# fullAdder.net
KiCad netlist of a schematic drawn in EAGLE
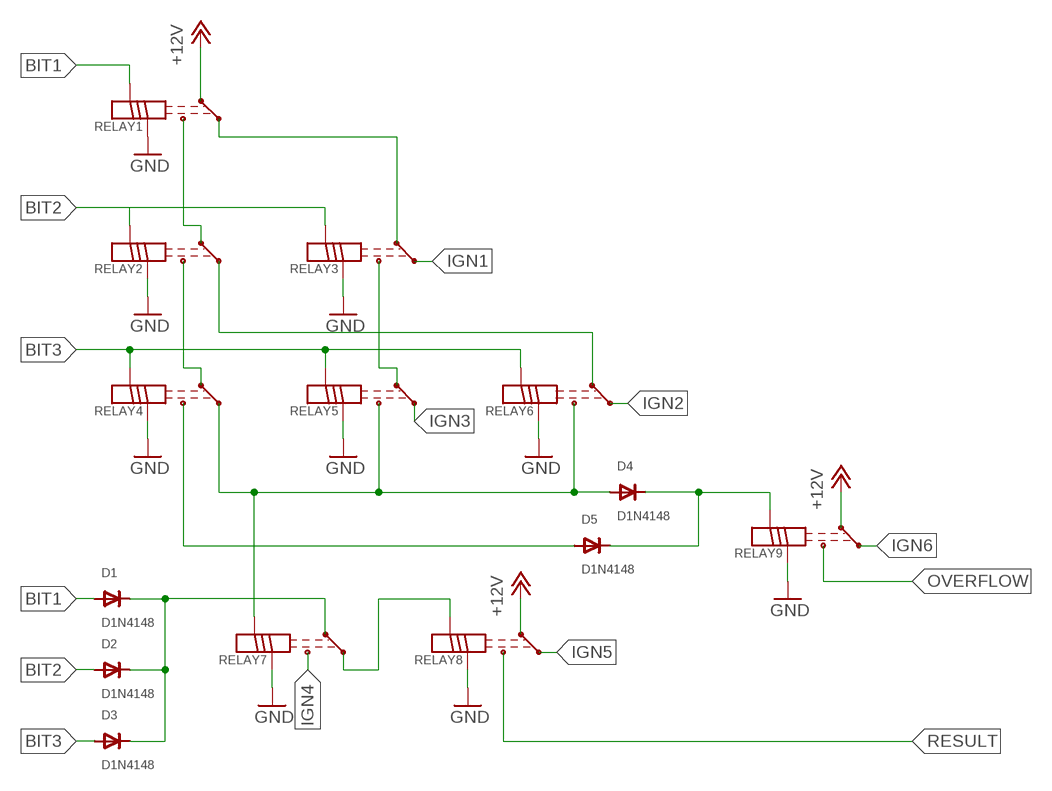
[diagram p0: schematic, sheet 1]

(export (version "E")
  (design (tool "Eeschema 10.0.6"))
  (components
    (comp (ref "D1")
      (value "D1N4148")
      (footprint "eagle-import:R0603")
      (libsource (lib "eagle-import") (part "DIODE"))
    )
    (comp (ref "D2")
      (value "D1N4148")
      (footprint "eagle-import:R0603")
      (libsource (lib "eagle-import") (part "DIODE"))
    )
    (comp (ref "D3")
      (value "D1N4148")
      (footprint "eagle-import:R0603")
      (libsource (lib "eagle-import") (part "DIODE"))
    )
    (comp (ref "D4")
      (value "D1N4148")
      (footprint "eagle-import:R0603")
      (libsource (lib "eagle-import") (part "DIODE"))
    )
    (comp (ref "D5")
      (value "D1N4148")
      (footprint "eagle-import:R0603")
      (libsource (lib "eagle-import") (part "DIODE"))
    )
    (comp (ref "RELAY1")
      (value "basicRelay")
      (footprint "eagle-import:RELAY-FINDER-40.51")
      (libsource (lib "eagle-import") (part "RELAY-GENERIC"))
    )
    (comp (ref "RELAY2")
      (value "basicRelay")
      (footprint "eagle-import:RELAY-FINDER-40.51")
      (libsource (lib "eagle-import") (part "RELAY-GENERIC"))
    )
    (comp (ref "RELAY3")
      (value "basicRelay")
      (footprint "eagle-import:RELAY-FINDER-40.51")
      (libsource (lib "eagle-import") (part "RELAY-GENERIC"))
    )
    (comp (ref "RELAY4")
      (value "basicRelay")
      (footprint "eagle-import:RELAY-FINDER-40.51")
      (libsource (lib "eagle-import") (part "RELAY-GENERIC"))
    )
    (comp (ref "RELAY5")
      (value "basicRelay")
      (footprint "eagle-import:RELAY-FINDER-40.51")
      (libsource (lib "eagle-import") (part "RELAY-GENERIC"))
    )
    (comp (ref "RELAY6")
      (value "basicRelay")
      (footprint "eagle-import:RELAY-FINDER-40.51")
      (libsource (lib "eagle-import") (part "RELAY-GENERIC"))
    )
    (comp (ref "RELAY7")
      (value "basicRelay")
      (footprint "eagle-import:RELAY-FINDER-40.51")
      (libsource (lib "eagle-import") (part "RELAY-GENERIC"))
    )
    (comp (ref "RELAY8")
      (value "basicRelay")
      (footprint "eagle-import:RELAY-FINDER-40.51")
      (libsource (lib "eagle-import") (part "RELAY-GENERIC"))
    )
    (comp (ref "RELAY9")
      (value "basicRelay")
      (footprint "eagle-import:RELAY-FINDER-40.51")
      (libsource (lib "eagle-import") (part "RELAY-GENERIC"))
    )
  )
  (nets
    (net (code "1") (name "+12V") (class "Default")
      (node (ref "RELAY1") (pin "CENTER") (pinfunction "CENTER_CENTER") (pintype "bidirectional"))
      (node (ref "RELAY8") (pin "CENTER") (pinfunction "CENTER_CENTER") (pintype "bidirectional"))
      (node (ref "RELAY9") (pin "CENTER") (pinfunction "CENTER_CENTER") (pintype "bidirectional"))
    )
    (net (code "2") (name "BIT1") (class "Default")
      (node (ref "D1") (pin "1") (pinfunction "ANODE_1") (pintype "bidirectional"))
      (node (ref "RELAY1") (pin "N+") (pinfunction "N+_N+") (pintype "bidirectional"))
    )
    (net (code "3") (name "BIT2") (class "Default")
      (node (ref "D2") (pin "1") (pinfunction "ANODE_1") (pintype "bidirectional"))
      (node (ref "RELAY2") (pin "N+") (pinfunction "N+_N+") (pintype "bidirectional"))
      (node (ref "RELAY3") (pin "N+") (pinfunction "N+_N+") (pintype "bidirectional"))
    )
    (net (code "4") (name "BIT3") (class "Default")
      (node (ref "D3") (pin "1") (pinfunction "ANODE_1") (pintype "bidirectional"))
      (node (ref "RELAY4") (pin "N+") (pinfunction "N+_N+") (pintype "bidirectional"))
      (node (ref "RELAY5") (pin "N+") (pinfunction "N+_N+") (pintype "bidirectional"))
      (node (ref "RELAY6") (pin "N+") (pinfunction "N+_N+") (pintype "bidirectional"))
    )
    (net (code "5") (name "GND") (class "Default")
      (node (ref "RELAY1") (pin "N-") (pinfunction "N-_N-") (pintype "bidirectional"))
      (node (ref "RELAY2") (pin "N-") (pinfunction "N-_N-") (pintype "bidirectional"))
      (node (ref "RELAY3") (pin "N-") (pinfunction "N-_N-") (pintype "bidirectional"))
      (node (ref "RELAY4") (pin "N-") (pinfunction "N-_N-") (pintype "bidirectional"))
      (node (ref "RELAY5") (pin "N-") (pinfunction "N-_N-") (pintype "bidirectional"))
      (node (ref "RELAY6") (pin "N-") (pinfunction "N-_N-") (pintype "bidirectional"))
      (node (ref "RELAY7") (pin "N-") (pinfunction "N-_N-") (pintype "bidirectional"))
      (node (ref "RELAY8") (pin "N-") (pinfunction "N-_N-") (pintype "bidirectional"))
      (node (ref "RELAY9") (pin "N-") (pinfunction "N-_N-") (pintype "bidirectional"))
    )
    (net (code "6") (name "IGN1") (class "Default")
      (node (ref "RELAY3") (pin "NCL") (pinfunction "NCL_NCL") (pintype "bidirectional"))
    )
    (net (code "7") (name "IGN2") (class "Default")
      (node (ref "RELAY6") (pin "NCL") (pinfunction "NCL_NCL") (pintype "bidirectional"))
    )
    (net (code "8") (name "IGN3") (class "Default")
      (node (ref "RELAY5") (pin "NCL") (pinfunction "NCL_NCL") (pintype "bidirectional"))
    )
    (net (code "9") (name "IGN4") (class "Default")
      (node (ref "RELAY7") (pin "NOP") (pinfunction "NOP_NOP") (pintype "bidirectional"))
    )
    (net (code "10") (name "IGN5") (class "Default")
      (node (ref "RELAY8") (pin "NCL") (pinfunction "NCL_NCL") (pintype "bidirectional"))
    )
    (net (code "11") (name "IGN6") (class "Default")
      (node (ref "RELAY9") (pin "NCL") (pinfunction "NCL_NCL") (pintype "bidirectional"))
    )
    (net (code "12") (name "Net-(D1-CATHODE)") (class "Default")
      (node (ref "D1") (pin "2") (pinfunction "CATHODE_2") (pintype "bidirectional"))
      (node (ref "D2") (pin "2") (pinfunction "CATHODE_2") (pintype "bidirectional"))
      (node (ref "D3") (pin "2") (pinfunction "CATHODE_2") (pintype "bidirectional"))
      (node (ref "RELAY7") (pin "CENTER") (pinfunction "CENTER_CENTER") (pintype "bidirectional"))
    )
    (net (code "13") (name "Net-(D4-ANODE)") (class "Default")
      (node (ref "D4") (pin "1") (pinfunction "ANODE_1") (pintype "bidirectional"))
      (node (ref "RELAY4") (pin "NCL") (pinfunction "NCL_NCL") (pintype "bidirectional"))
      (node (ref "RELAY5") (pin "NOP") (pinfunction "NOP_NOP") (pintype "bidirectional"))
      (node (ref "RELAY6") (pin "NOP") (pinfunction "NOP_NOP") (pintype "bidirectional"))
      (node (ref "RELAY7") (pin "N+") (pinfunction "N+_N+") (pintype "bidirectional"))
    )
    (net (code "14") (name "Net-(D4-CATHODE)") (class "Default")
      (node (ref "D4") (pin "2") (pinfunction "CATHODE_2") (pintype "bidirectional"))
      (node (ref "D5") (pin "2") (pinfunction "CATHODE_2") (pintype "bidirectional"))
      (node (ref "RELAY9") (pin "N+") (pinfunction "N+_N+") (pintype "bidirectional"))
    )
    (net (code "15") (name "Net-(D5-ANODE)") (class "Default")
      (node (ref "D5") (pin "1") (pinfunction "ANODE_1") (pintype "bidirectional"))
      (node (ref "RELAY4") (pin "NOP") (pinfunction "NOP_NOP") (pintype "bidirectional"))
    )
    (net (code "16") (name "Net-(RELAY1-PadNCL)") (class "Default")
      (node (ref "RELAY1") (pin "NCL") (pinfunction "NCL_NCL") (pintype "bidirectional"))
      (node (ref "RELAY3") (pin "CENTER") (pinfunction "CENTER_CENTER") (pintype "bidirectional"))
    )
    (net (code "17") (name "Net-(RELAY1-PadNOP)") (class "Default")
      (node (ref "RELAY1") (pin "NOP") (pinfunction "NOP_NOP") (pintype "bidirectional"))
      (node (ref "RELAY2") (pin "CENTER") (pinfunction "CENTER_CENTER") (pintype "bidirectional"))
    )
    (net (code "18") (name "Net-(RELAY2-PadNCL)") (class "Default")
      (node (ref "RELAY2") (pin "NCL") (pinfunction "NCL_NCL") (pintype "bidirectional"))
      (node (ref "RELAY6") (pin "CENTER") (pinfunction "CENTER_CENTER") (pintype "bidirectional"))
    )
    (net (code "19") (name "Net-(RELAY2-PadNOP)") (class "Default")
      (node (ref "RELAY2") (pin "NOP") (pinfunction "NOP_NOP") (pintype "bidirectional"))
      (node (ref "RELAY4") (pin "CENTER") (pinfunction "CENTER_CENTER") (pintype "bidirectional"))
    )
    (net (code "20") (name "Net-(RELAY3-PadNOP)") (class "Default")
      (node (ref "RELAY3") (pin "NOP") (pinfunction "NOP_NOP") (pintype "bidirectional"))
      (node (ref "RELAY5") (pin "CENTER") (pinfunction "CENTER_CENTER") (pintype "bidirectional"))
    )
    (net (code "21") (name "Net-(RELAY7-PadNCL)") (class "Default")
      (node (ref "RELAY7") (pin "NCL") (pinfunction "NCL_NCL") (pintype "bidirectional"))
      (node (ref "RELAY8") (pin "N+") (pinfunction "N+_N+") (pintype "bidirectional"))
    )
    (net (code "22") (name "OVERFLOW") (class "Default")
      (node (ref "RELAY9") (pin "NOP") (pinfunction "NOP_NOP") (pintype "bidirectional"))
    )
    (net (code "23") (name "RESULT") (class "Default")
      (node (ref "RELAY8") (pin "NOP") (pinfunction "NOP_NOP") (pintype "bidirectional"))
    )
  )
)
